# Serqet.net
KiCad netlist of a schematic drawn in EAGLE
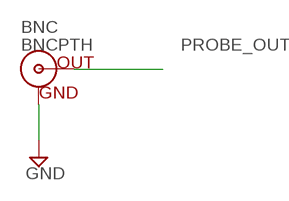
[diagram p0: schematic, sheet 1]
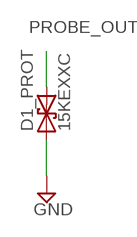
[diagram p1: schematic, sheet 2]
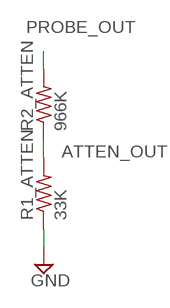
[diagram p2: schematic, sheet 3]
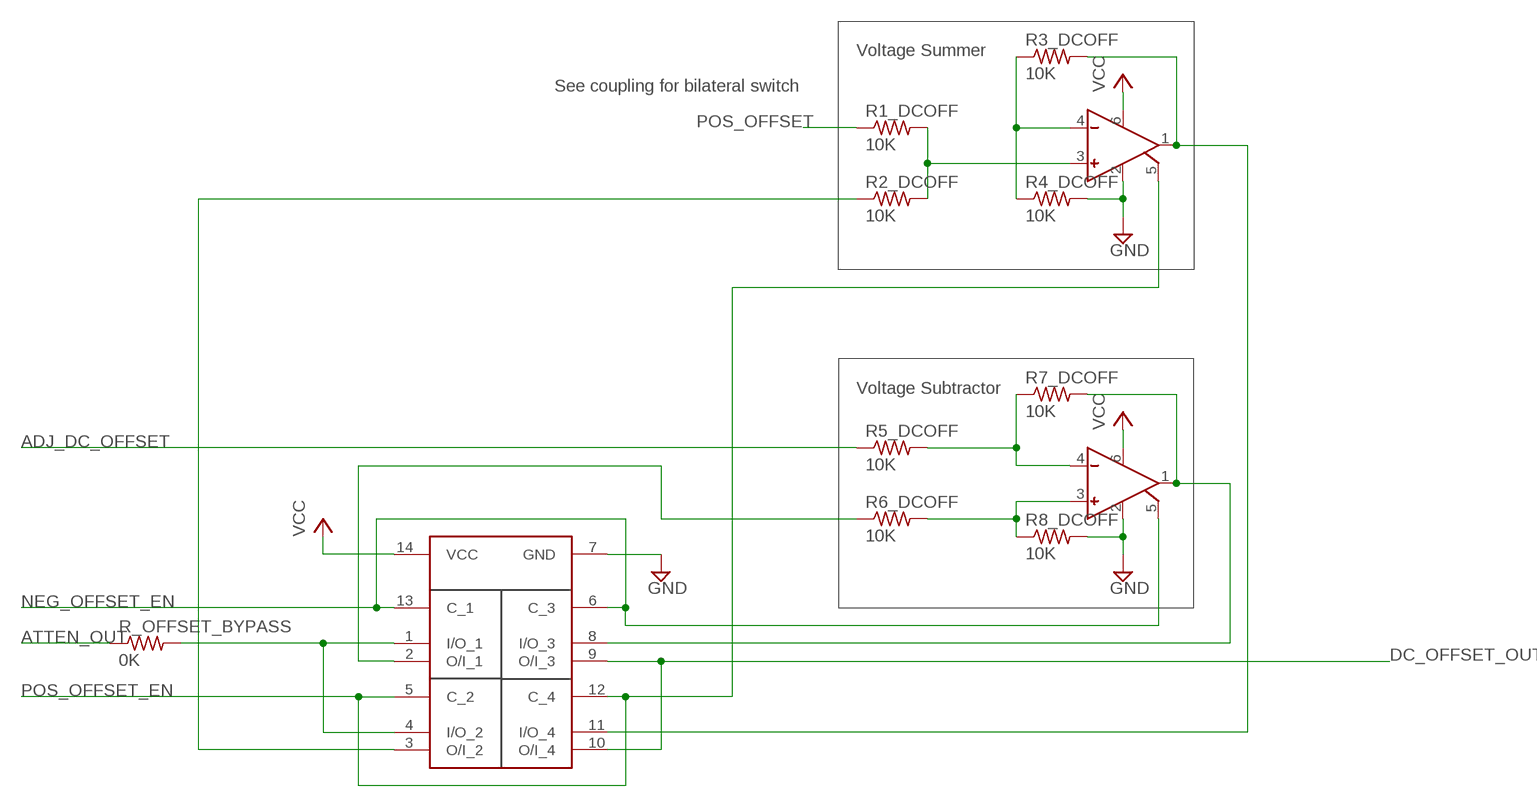
[diagram p3: schematic, sheet 4]
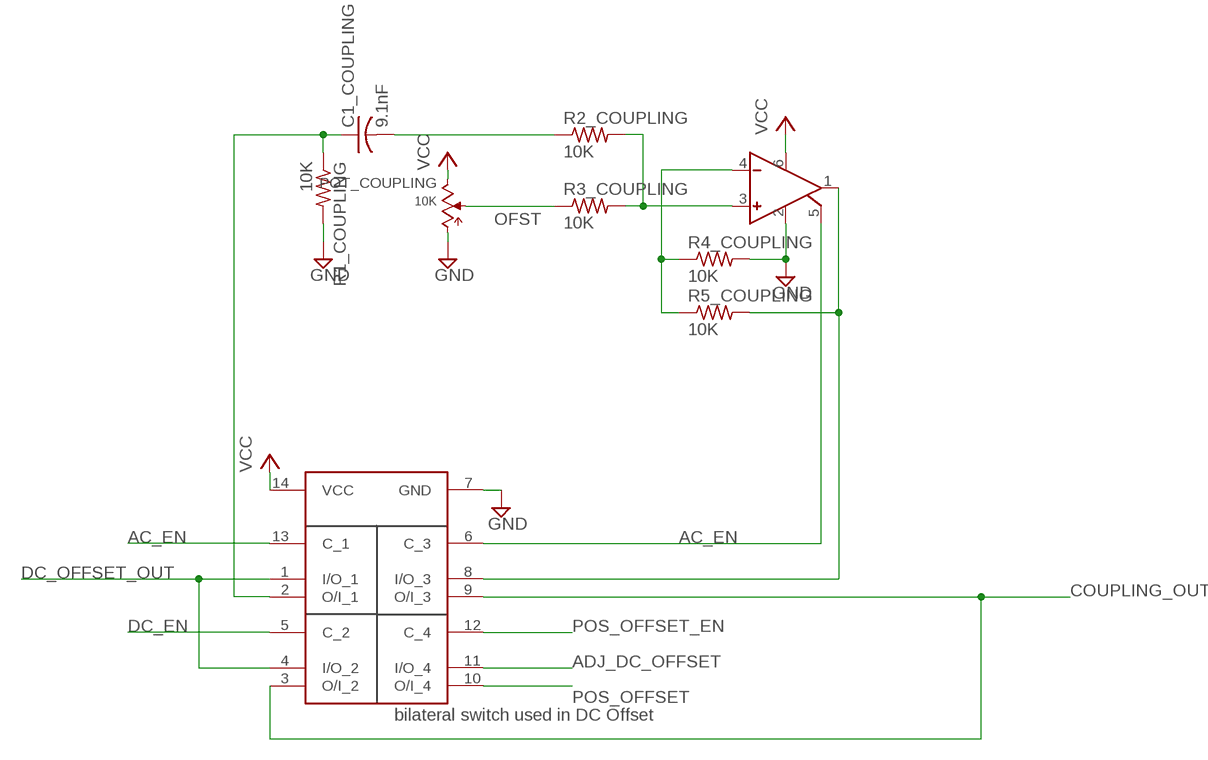
[diagram p4: schematic, sheet 5]
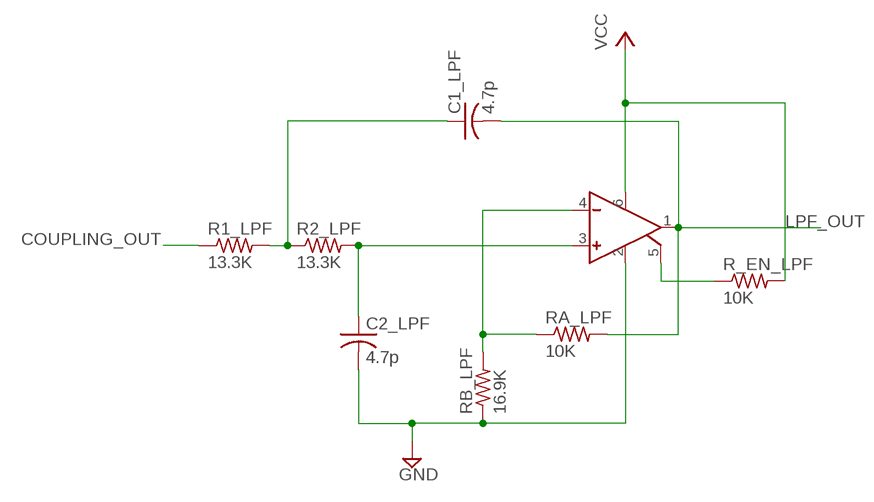
[diagram p5: schematic, sheet 6]
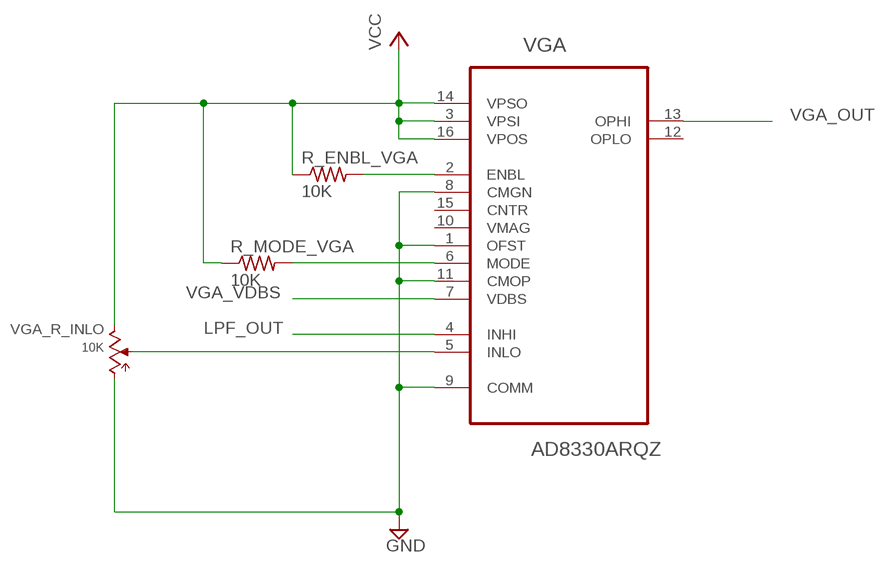
[diagram p6: schematic, sheet 7]
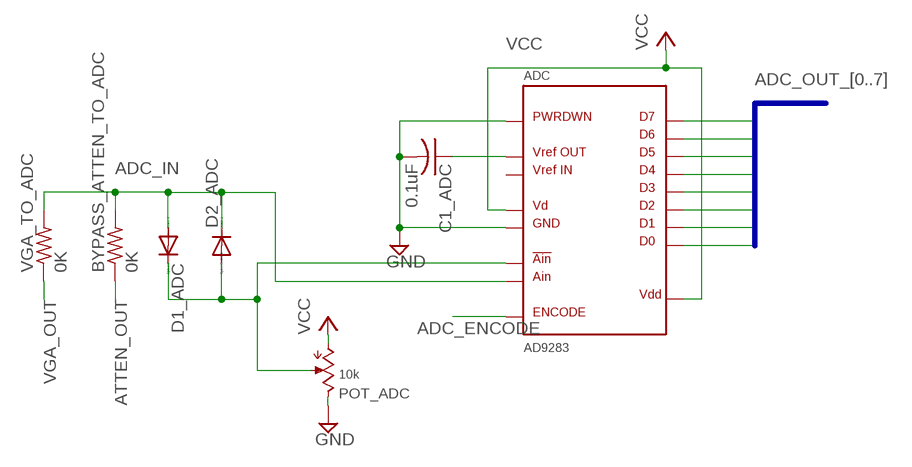
[diagram p7: schematic, sheet 8]
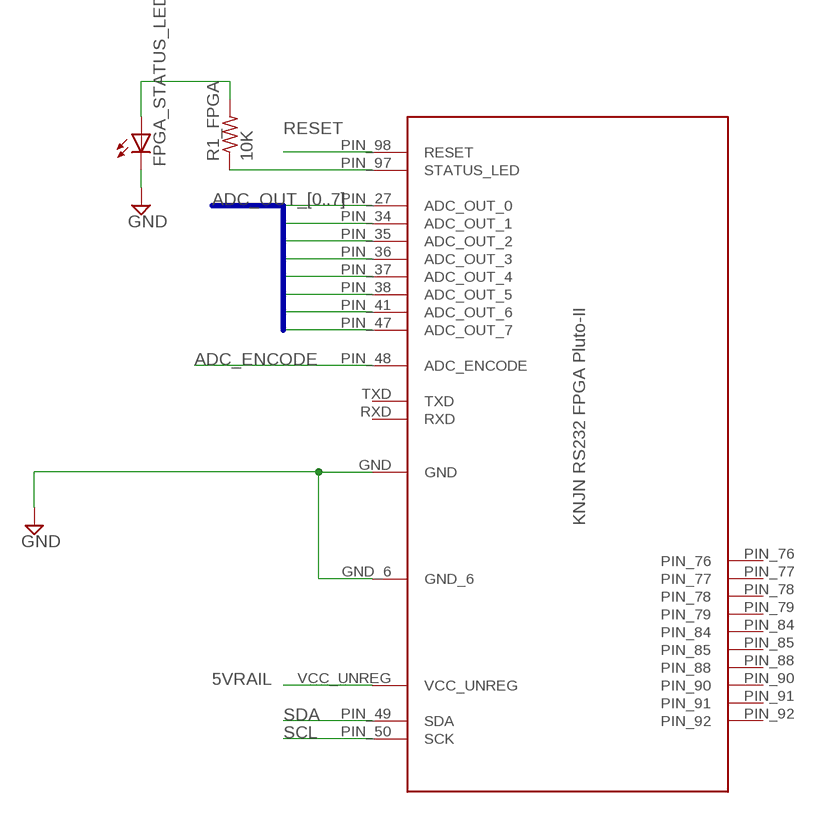
[diagram p8: schematic, sheet 9]
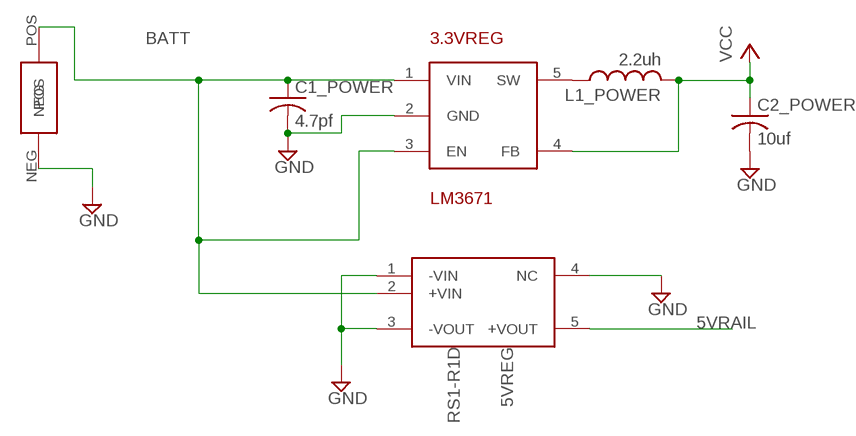
[diagram p9: schematic, sheet 10]
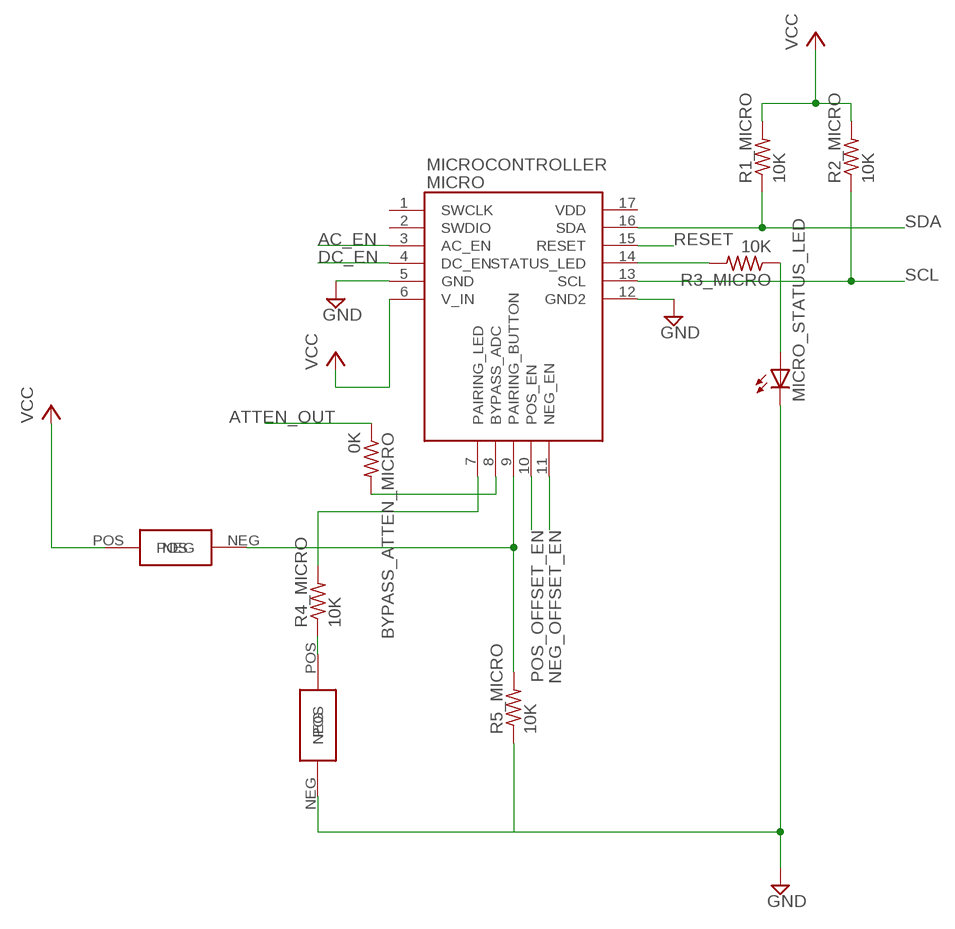
[diagram p10: schematic, sheet 11]
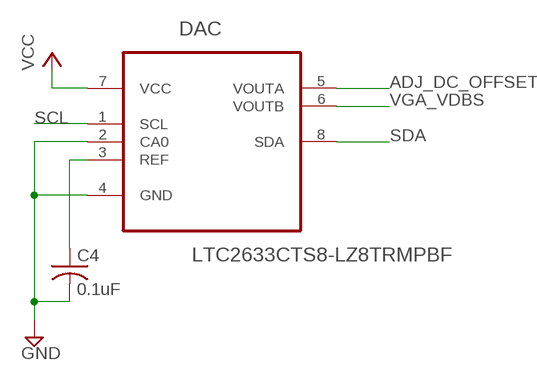
[diagram p11: schematic, sheet 12]

(export (version "E")
  (design (tool "Eeschema 10.0.6"))
  (components
    (comp (ref "BILATERAL_DCOFF")
      (value "TC74HC4066AFT")
      (footprint "eagle-import:TSSOP14")
      (libsource (lib "eagle-import") (part "TC74HC4066AFT"))
    )
    (comp (ref "OP_AMP1_DCOFF")
      (value "OPA355")
      (footprint "eagle-import:SOT23-6")
      (libsource (lib "eagle-import") (part "OPA355"))
    )
    (comp (ref "OP_AMP2_DCOFF")
      (value "OPA355")
      (footprint "eagle-import:SOT23-6")
      (libsource (lib "eagle-import") (part "OPA355"))
    )
    (comp (ref "R1_DCOFF")
      (value "10K")
      (footprint "eagle-import:R0603")
      (libsource (lib "eagle-import") (part "R-US_R0603"))
    )
    (comp (ref "R2_DCOFF")
      (value "10K")
      (footprint "eagle-import:R0603")
      (libsource (lib "eagle-import") (part "R-US_R0603"))
    )
    (comp (ref "R3_DCOFF")
      (value "10K")
      (footprint "eagle-import:R0603")
      (libsource (lib "eagle-import") (part "R-US_R0603"))
    )
    (comp (ref "R4_DCOFF")
      (value "10K")
      (footprint "eagle-import:R0603")
      (libsource (lib "eagle-import") (part "R-US_R0603"))
    )
    (comp (ref "R5_DCOFF")
      (value "10K")
      (footprint "eagle-import:R0603")
      (libsource (lib "eagle-import") (part "R-US_R0603"))
    )
    (comp (ref "R6_DCOFF")
      (value "10K")
      (footprint "eagle-import:R0603")
      (libsource (lib "eagle-import") (part "R-US_R0603"))
    )
    (comp (ref "R7_DCOFF")
      (value "10K")
      (footprint "eagle-import:R0603")
      (libsource (lib "eagle-import") (part "R-US_R0603"))
    )
    (comp (ref "R8_DCOFF")
      (value "10K")
      (footprint "eagle-import:R0603")
      (libsource (lib "eagle-import") (part "R-US_R0603"))
    )
    (comp (ref "R_OFFSET_BYPASS")
      (value "0K")
      (footprint "eagle-import:R0603")
      (libsource (lib "eagle-import") (part "R-US_R0603"))
    )
    (comp (ref "BILATERAL_COUPLING")
      (value "TC74HC4066AFT")
      (footprint "eagle-import:TSSOP14")
      (libsource (lib "eagle-import") (part "TC74HC4066AFT"))
    )
    (comp (ref "C1_COUPLING")
      (value "9.1nF")
      (footprint "eagle-import:C0603")
      (libsource (lib "eagle-import") (part "C-USC0603"))
    )
    (comp (ref "OP_AMP_COUPLING")
      (value "OPA355")
      (footprint "eagle-import:SOT23-6")
      (libsource (lib "eagle-import") (part "OPA355"))
    )
    (comp (ref "POT_COUPLING")
      (value "10K")
      (footprint "eagle-import:TRIMPOT_3HOLE_CHEAP")
      (libsource (lib "eagle-import") (part "POT-CHEAP_3HOLE_TRIM"))
    )
    (comp (ref "R1_COUPLING")
      (value "10K")
      (footprint "eagle-import:R0603")
      (libsource (lib "eagle-import") (part "R-US_R0603"))
    )
    (comp (ref "R2_COUPLING")
      (value "10K")
      (footprint "eagle-import:R0603")
      (libsource (lib "eagle-import") (part "R-US_R0603"))
    )
    (comp (ref "R3_COUPLING")
      (value "10K")
      (footprint "eagle-import:R0603")
      (libsource (lib "eagle-import") (part "R-US_R0603"))
    )
    (comp (ref "R4_COUPLING")
      (value "10K")
      (footprint "eagle-import:R0603")
      (libsource (lib "eagle-import") (part "R-US_R0603"))
    )
    (comp (ref "R5_COUPLING")
      (value "10K")
      (footprint "eagle-import:R0603")
      (libsource (lib "eagle-import") (part "R-US_R0603"))
    )
    (comp (ref "BYPASS_ATTEN_MICRO")
      (value "0K")
      (footprint "eagle-import:R0603")
      (libsource (lib "eagle-import") (part "resistor_R-US_R0603"))
    )
    (comp (ref "LED_THROUGHOLE")
      (value "LED_THROUGHHOLE")
      (footprint "eagle-import:LED_THROUGHHOLE")
      (libsource (lib "eagle-import") (part "LED_THROUGHHOLE"))
    )
    (comp (ref "MICRO")
      (value "MICROCONTROLLER")
      (footprint "eagle-import:MICROPROC")
      (libsource (lib "eagle-import") (part "MICROCONTROLLER"))
    )
    (comp (ref "MICRO_STATUS_LED")
      (value "LEDCHIP-LED0805")
      (footprint "eagle-import:CHIP-LED0805")
      (libsource (lib "eagle-import") (part "LEDCHIP-LED0805"))
    )
    (comp (ref "PAIRING_SWITCH")
      (value "LED_THROUGHHOLE")
      (footprint "eagle-import:LED_THROUGHHOLE")
      (libsource (lib "eagle-import") (part "LED_THROUGHHOLE"))
    )
    (comp (ref "R1_MICRO")
      (value "10K")
      (footprint "eagle-import:R0603")
      (libsource (lib "eagle-import") (part "resistor_R-US_R0603"))
    )
    (comp (ref "R2_MICRO")
      (value "10K")
      (footprint "eagle-import:R0603")
      (libsource (lib "eagle-import") (part "resistor_R-US_R0603"))
    )
    (comp (ref "R3_MICRO")
      (value "10K")
      (footprint "eagle-import:R0603")
      (libsource (lib "eagle-import") (part "resistor_R-US_R0603"))
    )
    (comp (ref "R4_MICRO")
      (value "10K")
      (footprint "eagle-import:R0603")
      (libsource (lib "eagle-import") (part "resistor_R-US_R0603"))
    )
    (comp (ref "R5_MICRO")
      (value "10K")
      (footprint "eagle-import:R0603")
      (libsource (lib "eagle-import") (part "R-US_R0603"))
    )
    (comp (ref "BNC")
      (value "BNCPTH")
      (footprint "eagle-import:BNC")
      (libsource (lib "eagle-import") (part "BNCPTH"))
    )
    (comp (ref "3.3VREG")
      (value "LM3671")
      (footprint "eagle-import:SOT23-5")
      (libsource (lib "eagle-import") (part "LM3671"))
    )
    (comp (ref "5VREG")
      (value "RS1-R1D")
      (footprint "eagle-import:8-SMD")
      (libsource (lib "eagle-import") (part "RS1-R1D"))
    )
    (comp (ref "BATTERY")
      (value "LED_THROUGHHOLE")
      (footprint "eagle-import:LED_THROUGHHOLE")
      (libsource (lib "eagle-import") (part "LED_THROUGHHOLE"))
    )
    (comp (ref "C1_POWER")
      (value "4.7pf")
      (footprint "eagle-import:C0603")
      (libsource (lib "eagle-import") (part "C-USC0603"))
    )
    (comp (ref "C2_POWER")
      (value "10uf")
      (footprint "eagle-import:C0603")
      (libsource (lib "eagle-import") (part "C-USC0603"))
    )
    (comp (ref "L1_POWER")
      (value "2.2uh")
      (footprint "eagle-import:L1812")
      (libsource (lib "eagle-import") (part "L-USL1008"))
    )
    (comp (ref "C1_LPF")
      (value "4.7p")
      (footprint "eagle-import:C0603")
      (libsource (lib "eagle-import") (part "C-USC0603"))
    )
    (comp (ref "C2_LPF")
      (value "4.7p")
      (footprint "eagle-import:C0603")
      (libsource (lib "eagle-import") (part "C-USC0603"))
    )
    (comp (ref "OP_AMP_LPF")
      (value "OPA355")
      (footprint "eagle-import:SOT23-6")
      (libsource (lib "eagle-import") (part "OPA355"))
    )
    (comp (ref "R1_LPF")
      (value "13.3K")
      (footprint "eagle-import:R0603")
      (libsource (lib "eagle-import") (part "R-US_R0603"))
    )
    (comp (ref "R2_LPF")
      (value "13.3K")
      (footprint "eagle-import:R0603")
      (libsource (lib "eagle-import") (part "R-US_R0603"))
    )
    (comp (ref "RA_LPF")
      (value "10K")
      (footprint "eagle-import:R0603")
      (libsource (lib "eagle-import") (part "R-US_R0603"))
    )
    (comp (ref "RB_LPF")
      (value "16.9K")
      (footprint "eagle-import:R0603")
      (libsource (lib "eagle-import") (part "R-US_R0603"))
    )
    (comp (ref "R_EN_LPF")
      (value "10K")
      (footprint "eagle-import:R0603")
      (libsource (lib "eagle-import") (part "R-US_R0603"))
    )
    (comp (ref "FPGA")
      (value "KNJNRS232FPGAPLUTO-IIKNJNRS232FPGAPLUTO-II")
      (footprint "eagle-import:KNJNRS232FPGAPLUTO-II")
      (libsource (lib "eagle-import") (part "KNJNRS232FPGAPLUTO-IIKNJNRS232FPGAPLUTO-II"))
    )
    (comp (ref "FPGA_STATUS_LED")
      (value "LEDCHIP-LED0805")
      (footprint "eagle-import:CHIP-LED0805")
      (libsource (lib "eagle-import") (part "LEDCHIP-LED0805"))
    )
    (comp (ref "R1_FPGA")
      (value "10K")
      (footprint "eagle-import:R0603")
      (libsource (lib "eagle-import") (part "resistor_R-US_R0603"))
    )
    (comp (ref "R_ENBL_VGA")
      (value "10K")
      (footprint "eagle-import:R0603")
      (libsource (lib "eagle-import") (part "R-US_R0603"))
    )
    (comp (ref "R_MODE_VGA")
      (value "10K")
      (footprint "eagle-import:R0603")
      (libsource (lib "eagle-import") (part "R-US_R0603"))
    )
    (comp (ref "VGA")
      (value "AD8330ARQZ")
      (footprint "eagle-import:SOP63P600X175-16N")
      (libsource (lib "eagle-import") (part "AD8330ARQZ"))
    )
    (comp (ref "VGA_R_INLO")
      (value "10K")
      (footprint "eagle-import:TRIMPOT_3HOLE_CHEAP")
      (libsource (lib "eagle-import") (part "POT-CHEAP_3HOLE_TRIM"))
    )
    (comp (ref "ADC")
      (value "AD9283")
      (footprint "eagle-import:SSOP20")
      (libsource (lib "eagle-import") (part "AD9283"))
    )
    (comp (ref "BYPASS_ATTEN_TO_ADC")
      (value "0K")
      (footprint "eagle-import:R0603")
      (libsource (lib "eagle-import") (part "resistor_R-US_R0603"))
    )
    (comp (ref "C1_ADC")
      (value "0.1uF")
      (footprint "eagle-import:C0603")
      (libsource (lib "eagle-import") (part "C-USC0603"))
    )
    (comp (ref "D1_ADC")
      (value "1N4933")
      (footprint "eagle-import:DO41-10")
      (libsource (lib "eagle-import") (part "1N4933"))
    )
    (comp (ref "D2_ADC")
      (value "1N4933")
      (footprint "eagle-import:DO41-10")
      (libsource (lib "eagle-import") (part "1N4933"))
    )
    (comp (ref "POT_ADC")
      (value "10k")
      (footprint "eagle-import:TRIMPOT_3HOLE_CHEAP")
      (libsource (lib "eagle-import") (part "POT-CHEAP_3HOLE_TRIM"))
    )
    (comp (ref "VGA_TO_ADC")
      (value "0K")
      (footprint "eagle-import:R0603")
      (libsource (lib "eagle-import") (part "resistor_R-US_R0603"))
    )
    (comp (ref "C4")
      (value "0.1uF")
      (footprint "eagle-import:C0603")
      (libsource (lib "eagle-import") (part "C-USC0603"))
    )
    (comp (ref "DAC")
      (value "LTC2633CTS8-LZ8TRMPBF")
      (footprint "eagle-import:SOT65P280X100-8N")
      (fields (field (name "MPN") "LTC2633CTS8-LZ8#TRMPBF"))
      (libsource (lib "eagle-import") (part "LTC2633CTS8-LZ8TRMPBF"))
    )
    (comp (ref "D1_PROT")
      (value "15KEXXC")
      (footprint "eagle-import:CB429-17")
      (libsource (lib "eagle-import") (part "15KEXXC"))
    )
    (comp (ref "R1_ATTEN")
      (value "33K")
      (footprint "eagle-import:R0603")
      (libsource (lib "eagle-import") (part "resistor_R-US_R0603"))
    )
    (comp (ref "R2_ATTEN")
      (value "966K")
      (footprint "eagle-import:R0603")
      (libsource (lib "eagle-import") (part "resistor_R-US_R0603"))
    )
  )
  (nets
    (net (code "3") (name "5VRAIL") (class "Default")
      (node (ref "5VREG") (pin "5") (pinfunction "+VOUT_5") (pintype "bidirectional"))
      (node (ref "FPGA") (pin "VCC_UNREG") (pinfunction "VCC_UNREG_VCC_UNREG") (pintype "bidirectional"))
    )
    (net (code "4") (name "AC_EN") (class "Default")
      (node (ref "BILATERAL_COUPLING") (pin "13") (pinfunction "C_1_13") (pintype "bidirectional"))
      (node (ref "BILATERAL_COUPLING") (pin "6") (pinfunction "C_3_6") (pintype "bidirectional"))
      (node (ref "MICRO") (pin "3") (pinfunction "AC_EN_3") (pintype "bidirectional"))
      (node (ref "OP_AMP_COUPLING") (pin "5") (pinfunction "ENABLE_5") (pintype "bidirectional"))
    )
    (net (code "5") (name "ADC_ENCODE") (class "Default")
      (node (ref "ADC") (pin "10") (pinfunction "ENCODE_10") (pintype "input"))
      (node (ref "FPGA") (pin "PIN_48") (pinfunction "ADC_ENCODE_PIN_48") (pintype "bidirectional"))
    )
    (net (code "6") (name "ADC_IN") (class "Default")
      (node (ref "ADC") (pin "7") (pinfunction "AIN_7") (pintype "input"))
      (node (ref "BYPASS_ATTEN_TO_ADC") (pin "2") (pinfunction "2_2") (pintype "passive"))
      (node (ref "D1_ADC") (pin "A") (pinfunction "A_A") (pintype "passive"))
      (node (ref "D2_ADC") (pin "C") (pinfunction "C_C") (pintype "passive"))
      (node (ref "VGA_TO_ADC") (pin "2") (pinfunction "2_2") (pintype "passive"))
    )
    (net (code "7") (name "ADC_OUT_0") (class "Default")
      (node (ref "ADC") (pin "20") (pinfunction "D0_20") (pintype "output"))
      (node (ref "FPGA") (pin "PIN_47") (pinfunction "ADC_OUT_7_PIN_47") (pintype "bidirectional"))
    )
    (net (code "8") (name "ADC_OUT_1") (class "Default")
      (node (ref "ADC") (pin "19") (pinfunction "D1_19") (pintype "output"))
      (node (ref "FPGA") (pin "PIN_41") (pinfunction "ADC_OUT_6_PIN_41") (pintype "bidirectional"))
    )
    (net (code "9") (name "ADC_OUT_2") (class "Default")
      (node (ref "ADC") (pin "18") (pinfunction "D2_18") (pintype "output"))
      (node (ref "FPGA") (pin "PIN_38") (pinfunction "ADC_OUT_5_PIN_38") (pintype "bidirectional"))
    )
    (net (code "10") (name "ADC_OUT_3") (class "Default")
      (node (ref "ADC") (pin "17") (pinfunction "D3_17") (pintype "output"))
      (node (ref "FPGA") (pin "PIN_37") (pinfunction "ADC_OUT_4_PIN_37") (pintype "bidirectional"))
    )
    (net (code "11") (name "ADC_OUT_4") (class "Default")
      (node (ref "ADC") (pin "14") (pinfunction "D4_14") (pintype "output"))
      (node (ref "FPGA") (pin "PIN_36") (pinfunction "ADC_OUT_3_PIN_36") (pintype "bidirectional"))
    )
    (net (code "12") (name "ADC_OUT_5") (class "Default")
      (node (ref "ADC") (pin "13") (pinfunction "D5_13") (pintype "output"))
      (node (ref "FPGA") (pin "PIN_35") (pinfunction "ADC_OUT_2_PIN_35") (pintype "bidirectional"))
    )
    (net (code "13") (name "ADC_OUT_6") (class "Default")
      (node (ref "ADC") (pin "12") (pinfunction "D6_12") (pintype "output"))
      (node (ref "FPGA") (pin "PIN_34") (pinfunction "ADC_OUT_1_PIN_34") (pintype "bidirectional"))
    )
    (net (code "14") (name "ADC_OUT_7") (class "Default")
      (node (ref "ADC") (pin "11") (pinfunction "D7_11") (pintype "output"))
      (node (ref "FPGA") (pin "PIN_27") (pinfunction "ADC_OUT_0_PIN_27") (pintype "bidirectional"))
    )
    (net (code "15") (name "ADJ_DC_OFFSET") (class "Default")
      (node (ref "BILATERAL_COUPLING") (pin "11") (pinfunction "I/O_4_11") (pintype "bidirectional"))
      (node (ref "DAC") (pin "5") (pinfunction "VOUTA_5") (pintype "output"))
      (node (ref "R5_DCOFF") (pin "1") (pinfunction "1_1") (pintype "passive"))
    )
    (net (code "16") (name "ATTEN_OUT") (class "Default")
      (node (ref "BYPASS_ATTEN_MICRO") (pin "1") (pinfunction "1_1") (pintype "passive"))
      (node (ref "BYPASS_ATTEN_TO_ADC") (pin "1") (pinfunction "1_1") (pintype "passive"))
      (node (ref "R1_ATTEN") (pin "2") (pinfunction "2_2") (pintype "passive"))
      (node (ref "R2_ATTEN") (pin "1") (pinfunction "1_1") (pintype "passive"))
      (node (ref "R_OFFSET_BYPASS") (pin "1") (pinfunction "1_1") (pintype "passive"))
    )
    (net (code "17") (name "BATT") (class "Default")
      (node (ref "3.3VREG") (pin "1") (pinfunction "VIN_1") (pintype "bidirectional"))
      (node (ref "3.3VREG") (pin "3") (pinfunction "EN_3") (pintype "bidirectional"))
      (node (ref "5VREG") (pin "2") (pinfunction "+VIN_2") (pintype "bidirectional"))
      (node (ref "BATTERY") (pin "POS") (pinfunction "POS_POS") (pintype "bidirectional"))
      (node (ref "C1_POWER") (pin "1") (pinfunction "1_1") (pintype "passive"))
    )
    (net (code "18") (name "COUPLING_OUT") (class "Default")
      (node (ref "BILATERAL_COUPLING") (pin "3") (pinfunction "O/I_2_3") (pintype "bidirectional"))
      (node (ref "BILATERAL_COUPLING") (pin "9") (pinfunction "O/I_3_9") (pintype "bidirectional"))
      (node (ref "R1_LPF") (pin "1") (pinfunction "1_1") (pintype "passive"))
    )
    (net (code "19") (name "DC_EN") (class "Default")
      (node (ref "BILATERAL_COUPLING") (pin "5") (pinfunction "C_2_5") (pintype "bidirectional"))
      (node (ref "MICRO") (pin "4") (pinfunction "DC_EN_4") (pintype "bidirectional"))
    )
    (net (code "20") (name "DC_OFFSET_OUT") (class "Default")
      (node (ref "BILATERAL_COUPLING") (pin "1") (pinfunction "I/O_1_1") (pintype "bidirectional"))
      (node (ref "BILATERAL_COUPLING") (pin "4") (pinfunction "I/O_2_4") (pintype "bidirectional"))
      (node (ref "BILATERAL_DCOFF") (pin "10") (pinfunction "O/I_4_10") (pintype "bidirectional"))
      (node (ref "BILATERAL_DCOFF") (pin "9") (pinfunction "O/I_3_9") (pintype "bidirectional"))
    )
    (net (code "21") (name "GND") (class "Default")
      (node (ref "3.3VREG") (pin "2") (pinfunction "GND_2") (pintype "bidirectional"))
      (node (ref "5VREG") (pin "1") (pinfunction "-VIN_1") (pintype "bidirectional"))
      (node (ref "5VREG") (pin "3") (pinfunction "-VOUT_3") (pintype "bidirectional"))
      (node (ref "5VREG") (pin "4") (pinfunction "NC_4") (pintype "bidirectional"))
      (node (ref "ADC") (pin "1") (pinfunction "PWRDWN_1") (pintype "input"))
      (node (ref "ADC") (pin "16") (pinfunction "GND_16") (pintype "power_in"))
      (node (ref "ADC") (pin "4") (pinfunction "GND_4") (pintype "power_in"))
      (node (ref "ADC") (pin "9") (pinfunction "GND_9") (pintype "power_in"))
      (node (ref "BATTERY") (pin "NEG") (pinfunction "NEG_NEG") (pintype "bidirectional"))
      (node (ref "BILATERAL_COUPLING") (pin "7") (pinfunction "GND_7") (pintype "bidirectional"))
      (node (ref "BILATERAL_DCOFF") (pin "7") (pinfunction "GND_7") (pintype "bidirectional"))
      (node (ref "BNC") (pin "GND") (pinfunction "GND_GND") (pintype "bidirectional"))
      (node (ref "C1_ADC") (pin "2") (pinfunction "2_2") (pintype "passive"))
      (node (ref "C1_POWER") (pin "2") (pinfunction "2_2") (pintype "passive"))
      (node (ref "C2_LPF") (pin "2") (pinfunction "2_2") (pintype "passive"))
      (node (ref "C2_POWER") (pin "2") (pinfunction "2_2") (pintype "passive"))
      (node (ref "C4") (pin "2") (pinfunction "2_2") (pintype "passive"))
      (node (ref "D1_PROT") (pin "A") (pinfunction "1_A") (pintype "passive"))
      (node (ref "DAC") (pin "2") (pinfunction "CA0_2") (pintype "input"))
      (node (ref "DAC") (pin "4") (pinfunction "GND_4") (pintype "passive"))
      (node (ref "FPGA") (pin "GND") (pinfunction "GND_GND") (pintype "bidirectional"))
      (node (ref "FPGA") (pin "GND_6") (pinfunction "GND_6_GND_6") (pintype "bidirectional"))
      (node (ref "FPGA_STATUS_LED") (pin "C") (pinfunction "C_C") (pintype "passive"))
      (node (ref "LED_THROUGHOLE") (pin "NEG") (pinfunction "NEG_NEG") (pintype "bidirectional"))
      (node (ref "MICRO") (pin "12") (pinfunction "GND2_12") (pintype "bidirectional"))
      (node (ref "MICRO") (pin "5") (pinfunction "GND_5") (pintype "bidirectional"))
      (node (ref "MICRO_STATUS_LED") (pin "C") (pinfunction "C_C") (pintype "passive"))
      (node (ref "OP_AMP1_DCOFF") (pin "2") (pinfunction "GND_2") (pintype "bidirectional"))
      (node (ref "OP_AMP2_DCOFF") (pin "2") (pinfunction "GND_2") (pintype "bidirectional"))
      (node (ref "OP_AMP_COUPLING") (pin "2") (pinfunction "GND_2") (pintype "bidirectional"))
      (node (ref "OP_AMP_LPF") (pin "2") (pinfunction "GND_2") (pintype "bidirectional"))
      (node (ref "POT_ADC") (pin "CW") (pinfunction "CW_CW") (pintype "bidirectional"))
      (node (ref "POT_COUPLING") (pin "CCW") (pinfunction "CCW_CCW") (pintype "bidirectional"))
      (node (ref "R1_ATTEN") (pin "1") (pinfunction "1_1") (pintype "passive"))
      (node (ref "R1_COUPLING") (pin "2") (pinfunction "2_2") (pintype "passive"))
      (node (ref "R4_COUPLING") (pin "2") (pinfunction "2_2") (pintype "passive"))
      (node (ref "R4_DCOFF") (pin "2") (pinfunction "2_2") (pintype "passive"))
      (node (ref "R5_MICRO") (pin "1") (pinfunction "1_1") (pintype "passive"))
      (node (ref "R8_DCOFF") (pin "2") (pinfunction "2_2") (pintype "passive"))
      (node (ref "RB_LPF") (pin "1") (pinfunction "1_1") (pintype "passive"))
      (node (ref "VGA") (pin "1") (pinfunction "OFST_1") (pintype "passive"))
      (node (ref "VGA") (pin "11") (pinfunction "CMOP_11") (pintype "passive"))
      (node (ref "VGA") (pin "8") (pinfunction "CMGN_8") (pintype "passive"))
      (node (ref "VGA") (pin "9") (pinfunction "COMM_9") (pintype "input"))
      (node (ref "VGA_R_INLO") (pin "CCW") (pinfunction "CCW_CCW") (pintype "bidirectional"))
    )
    (net (code "22") (name "LPF_OUT") (class "Default")
      (node (ref "C1_LPF") (pin "2") (pinfunction "2_2") (pintype "passive"))
      (node (ref "OP_AMP_LPF") (pin "1") (pinfunction "OUT_1") (pintype "bidirectional"))
      (node (ref "RA_LPF") (pin "2") (pinfunction "2_2") (pintype "passive"))
      (node (ref "VGA") (pin "4") (pinfunction "INHI_4") (pintype "input"))
    )
    (net (code "23") (name "N$22") (class "Default")
      (node (ref "BILATERAL_DCOFF") (pin "3") (pinfunction "O/I_2_3") (pintype "bidirectional"))
      (node (ref "MICRO") (pin "9") (pinfunction "PAIRING_BUTTON_9") (pintype "bidirectional"))
      (node (ref "PAIRING_SWITCH") (pin "NEG") (pinfunction "NEG_NEG") (pintype "bidirectional"))
      (node (ref "R2_DCOFF") (pin "1") (pinfunction "1_1") (pintype "passive"))
      (node (ref "R5_MICRO") (pin "2") (pinfunction "2_2") (pintype "passive"))
    )
    (net (code "24") (name "NEG_OFFSET_EN") (class "Default")
      (node (ref "BILATERAL_DCOFF") (pin "13") (pinfunction "C_1_13") (pintype "bidirectional"))
      (node (ref "BILATERAL_DCOFF") (pin "6") (pinfunction "C_3_6") (pintype "bidirectional"))
      (node (ref "MICRO") (pin "11") (pinfunction "NEG_EN_11") (pintype "bidirectional"))
      (node (ref "OP_AMP2_DCOFF") (pin "5") (pinfunction "ENABLE_5") (pintype "bidirectional"))
    )
    (net (code "25") (name "Net-(3.3VREG-SW)") (class "Default")
      (node (ref "3.3VREG") (pin "5") (pinfunction "SW_5") (pintype "bidirectional"))
      (node (ref "L1_POWER") (pin "1") (pinfunction "1_1") (pintype "passive"))
    )
    (net (code "26") (name "Net-(ADC-VREFOUT)") (class "Default")
      (node (ref "ADC") (pin "2") (pinfunction "VREFOUT_2") (pintype "power_in"))
      (node (ref "C1_ADC") (pin "1") (pinfunction "1_1") (pintype "passive"))
    )
    (net (code "27") (name "Net-(ADC-~{AIN})") (class "Default")
      (node (ref "ADC") (pin "6") (pinfunction "~{AIN}_6") (pintype "input"))
      (node (ref "D1_ADC") (pin "C") (pinfunction "C_C") (pintype "passive"))
      (node (ref "D2_ADC") (pin "A") (pinfunction "A_A") (pintype "passive"))
      (node (ref "POT_ADC") (pin "W") (pinfunction "W_W") (pintype "bidirectional"))
    )
    (net (code "28") (name "Net-(BILATERAL_COUPLING-I{slash}O_3)") (class "Default")
      (node (ref "BILATERAL_COUPLING") (pin "8") (pinfunction "I/O_3_8") (pintype "bidirectional"))
      (node (ref "OP_AMP_COUPLING") (pin "1") (pinfunction "OUT_1") (pintype "bidirectional"))
      (node (ref "R5_COUPLING") (pin "2") (pinfunction "2_2") (pintype "passive"))
    )
    (net (code "29") (name "Net-(BILATERAL_COUPLING-O{slash}I_1)") (class "Default")
      (node (ref "BILATERAL_COUPLING") (pin "2") (pinfunction "O/I_1_2") (pintype "bidirectional"))
      (node (ref "C1_COUPLING") (pin "1") (pinfunction "1_1") (pintype "passive"))
      (node (ref "R1_COUPLING") (pin "1") (pinfunction "1_1") (pintype "passive"))
    )
    (net (code "30") (name "Net-(BILATERAL_DCOFF-I{slash}O_1)") (class "Default")
      (node (ref "BILATERAL_DCOFF") (pin "1") (pinfunction "I/O_1_1") (pintype "bidirectional"))
      (node (ref "BILATERAL_DCOFF") (pin "4") (pinfunction "I/O_2_4") (pintype "bidirectional"))
      (node (ref "R_OFFSET_BYPASS") (pin "2") (pinfunction "2_2") (pintype "passive"))
    )
    (net (code "31") (name "Net-(BILATERAL_DCOFF-I{slash}O_3)") (class "Default")
      (node (ref "BILATERAL_DCOFF") (pin "8") (pinfunction "I/O_3_8") (pintype "bidirectional"))
      (node (ref "OP_AMP2_DCOFF") (pin "1") (pinfunction "OUT_1") (pintype "bidirectional"))
      (node (ref "R7_DCOFF") (pin "2") (pinfunction "2_2") (pintype "passive"))
    )
    (net (code "32") (name "Net-(BILATERAL_DCOFF-I{slash}O_4)") (class "Default")
      (node (ref "BILATERAL_DCOFF") (pin "11") (pinfunction "I/O_4_11") (pintype "bidirectional"))
      (node (ref "OP_AMP1_DCOFF") (pin "1") (pinfunction "OUT_1") (pintype "bidirectional"))
      (node (ref "R3_DCOFF") (pin "2") (pinfunction "2_2") (pintype "passive"))
    )
    (net (code "33") (name "Net-(BILATERAL_DCOFF-O{slash}I_1)") (class "Default")
      (node (ref "BILATERAL_DCOFF") (pin "2") (pinfunction "O/I_1_2") (pintype "bidirectional"))
      (node (ref "R6_DCOFF") (pin "1") (pinfunction "1_1") (pintype "passive"))
    )
    (net (code "34") (name "Net-(C1_COUPLING-Pad2)") (class "Default")
      (node (ref "C1_COUPLING") (pin "2") (pinfunction "2_2") (pintype "passive"))
      (node (ref "R2_COUPLING") (pin "1") (pinfunction "1_1") (pintype "passive"))
    )
    (net (code "35") (name "Net-(C1_LPF-Pad1)") (class "Default")
      (node (ref "C1_LPF") (pin "1") (pinfunction "1_1") (pintype "passive"))
      (node (ref "R1_LPF") (pin "2") (pinfunction "2_2") (pintype "passive"))
      (node (ref "R2_LPF") (pin "1") (pinfunction "1_1") (pintype "passive"))
    )
    (net (code "36") (name "Net-(DAC-REF)") (class "Default")
      (node (ref "C4") (pin "1") (pinfunction "1_1") (pintype "passive"))
      (node (ref "DAC") (pin "3") (pinfunction "REF_3") (pintype "input"))
    )
    (net (code "37") (name "Net-(FPGA-STATUS_LED)") (class "Default")
      (node (ref "FPGA") (pin "PIN_97") (pinfunction "STATUS_LED_PIN_97") (pintype "bidirectional"))
      (node (ref "R1_FPGA") (pin "1") (pinfunction "1_1") (pintype "passive"))
    )
    (net (code "38") (name "Net-(FPGA_STATUS_LED-PadA)") (class "Default")
      (node (ref "FPGA_STATUS_LED") (pin "A") (pinfunction "A_A") (pintype "passive"))
      (node (ref "R1_FPGA") (pin "2") (pinfunction "2_2") (pintype "passive"))
    )
    (net (code "39") (name "Net-(LED_THROUGHOLE-PadPOS)") (class "Default")
      (node (ref "LED_THROUGHOLE") (pin "POS") (pinfunction "POS_POS") (pintype "bidirectional"))
      (node (ref "R4_MICRO") (pin "1") (pinfunction "1_1") (pintype "passive"))
    )
    (net (code "40") (name "Net-(MICRO-BYPASS_ADC)") (class "Default")
      (node (ref "BYPASS_ATTEN_MICRO") (pin "2") (pinfunction "2_2") (pintype "passive"))
      (node (ref "MICRO") (pin "8") (pinfunction "BYPASS_ADC_8") (pintype "bidirectional"))
    )
    (net (code "41") (name "Net-(MICRO-PAIRING_LED)") (class "Default")
      (node (ref "MICRO") (pin "7") (pinfunction "PAIRING_LED_7") (pintype "bidirectional"))
      (node (ref "R4_MICRO") (pin "2") (pinfunction "2_2") (pintype "passive"))
    )
    (net (code "42") (name "Net-(MICRO-STATUS_LED)") (class "Default")
      (node (ref "MICRO") (pin "14") (pinfunction "STATUS_LED_14") (pintype "bidirectional"))
      (node (ref "R3_MICRO") (pin "2") (pinfunction "2_2") (pintype "passive"))
    )
    (net (code "43") (name "Net-(MICRO_STATUS_LED-PadA)") (class "Default")
      (node (ref "MICRO_STATUS_LED") (pin "A") (pinfunction "A_A") (pintype "passive"))
      (node (ref "R3_MICRO") (pin "1") (pinfunction "1_1") (pintype "passive"))
    )
    (net (code "44") (name "Net-(OP_AMP1_DCOFF-V+)") (class "Default")
      (node (ref "OP_AMP1_DCOFF") (pin "3") (pinfunction "V+_3") (pintype "bidirectional"))
      (node (ref "R1_DCOFF") (pin "2") (pinfunction "2_2") (pintype "passive"))
      (node (ref "R2_DCOFF") (pin "2") (pinfunction "2_2") (pintype "passive"))
    )
    (net (code "45") (name "Net-(OP_AMP1_DCOFF-V-)") (class "Default")
      (node (ref "OP_AMP1_DCOFF") (pin "4") (pinfunction "V-_4") (pintype "bidirectional"))
      (node (ref "R3_DCOFF") (pin "1") (pinfunction "1_1") (pintype "passive"))
      (node (ref "R4_DCOFF") (pin "1") (pinfunction "1_1") (pintype "passive"))
    )
    (net (code "46") (name "Net-(OP_AMP2_DCOFF-V+)") (class "Default")
      (node (ref "OP_AMP2_DCOFF") (pin "3") (pinfunction "V+_3") (pintype "bidirectional"))
      (node (ref "R6_DCOFF") (pin "2") (pinfunction "2_2") (pintype "passive"))
      (node (ref "R8_DCOFF") (pin "1") (pinfunction "1_1") (pintype "passive"))
    )
    (net (code "47") (name "Net-(OP_AMP2_DCOFF-V-)") (class "Default")
      (node (ref "OP_AMP2_DCOFF") (pin "4") (pinfunction "V-_4") (pintype "bidirectional"))
      (node (ref "R5_DCOFF") (pin "2") (pinfunction "2_2") (pintype "passive"))
      (node (ref "R7_DCOFF") (pin "1") (pinfunction "1_1") (pintype "passive"))
    )
    (net (code "48") (name "Net-(OP_AMP_COUPLING-V+)") (class "Default")
      (node (ref "OP_AMP_COUPLING") (pin "3") (pinfunction "V+_3") (pintype "bidirectional"))
      (node (ref "R2_COUPLING") (pin "2") (pinfunction "2_2") (pintype "passive"))
      (node (ref "R3_COUPLING") (pin "2") (pinfunction "2_2") (pintype "passive"))
    )
    (net (code "49") (name "Net-(OP_AMP_COUPLING-V-)") (class "Default")
      (node (ref "OP_AMP_COUPLING") (pin "4") (pinfunction "V-_4") (pintype "bidirectional"))
      (node (ref "R4_COUPLING") (pin "1") (pinfunction "1_1") (pintype "passive"))
      (node (ref "R5_COUPLING") (pin "1") (pinfunction "1_1") (pintype "passive"))
    )
    (net (code "50") (name "Net-(OP_AMP_LPF-ENABLE)") (class "Default")
      (node (ref "OP_AMP_LPF") (pin "5") (pinfunction "ENABLE_5") (pintype "bidirectional"))
      (node (ref "R_EN_LPF") (pin "1") (pinfunction "1_1") (pintype "passive"))
    )
    (net (code "51") (name "Net-(OP_AMP_LPF-V+)") (class "Default")
      (node (ref "C2_LPF") (pin "1") (pinfunction "1_1") (pintype "passive"))
      (node (ref "OP_AMP_LPF") (pin "3") (pinfunction "V+_3") (pintype "bidirectional"))
      (node (ref "R2_LPF") (pin "2") (pinfunction "2_2") (pintype "passive"))
    )
    (net (code "52") (name "Net-(OP_AMP_LPF-V-)") (class "Default")
      (node (ref "OP_AMP_LPF") (pin "4") (pinfunction "V-_4") (pintype "bidirectional"))
      (node (ref "RA_LPF") (pin "1") (pinfunction "1_1") (pintype "passive"))
      (node (ref "RB_LPF") (pin "2") (pinfunction "2_2") (pintype "passive"))
    )
    (net (code "53") (name "Net-(VGA-ENBL)") (class "Default")
      (node (ref "R_ENBL_VGA") (pin "2") (pinfunction "2_2") (pintype "passive"))
      (node (ref "VGA") (pin "2") (pinfunction "ENBL_2") (pintype "input"))
    )
    (net (code "54") (name "Net-(VGA-INLO)") (class "Default")
      (node (ref "VGA") (pin "5") (pinfunction "INLO_5") (pintype "input"))
      (node (ref "VGA_R_INLO") (pin "W") (pinfunction "W_W") (pintype "bidirectional"))
    )
    (net (code "55") (name "Net-(VGA-MODE)") (class "Default")
      (node (ref "R_MODE_VGA") (pin "2") (pinfunction "2_2") (pintype "passive"))
      (node (ref "VGA") (pin "6") (pinfunction "MODE_6") (pintype "input"))
    )
    (net (code "56") (name "OFST") (class "Default")
      (node (ref "POT_COUPLING") (pin "W") (pinfunction "W_W") (pintype "bidirectional"))
      (node (ref "R3_COUPLING") (pin "1") (pinfunction "1_1") (pintype "passive"))
    )
    (net (code "57") (name "POS_OFFSET") (class "Default")
      (node (ref "BILATERAL_COUPLING") (pin "10") (pinfunction "O/I_4_10") (pintype "bidirectional"))
      (node (ref "R1_DCOFF") (pin "1") (pinfunction "1_1") (pintype "passive"))
    )
    (net (code "58") (name "POS_OFFSET_EN") (class "Default")
      (node (ref "BILATERAL_COUPLING") (pin "12") (pinfunction "C_4_12") (pintype "bidirectional"))
      (node (ref "BILATERAL_DCOFF") (pin "12") (pinfunction "C_4_12") (pintype "bidirectional"))
      (node (ref "BILATERAL_DCOFF") (pin "5") (pinfunction "C_2_5") (pintype "bidirectional"))
      (node (ref "MICRO") (pin "10") (pinfunction "POS_EN_10") (pintype "bidirectional"))
      (node (ref "OP_AMP1_DCOFF") (pin "5") (pinfunction "ENABLE_5") (pintype "bidirectional"))
    )
    (net (code "59") (name "PROBE_OUT") (class "Default")
      (node (ref "BNC") (pin "S") (pinfunction "OUT_S") (pintype "bidirectional"))
      (node (ref "D1_PROT") (pin "C") (pinfunction "2_C") (pintype "passive"))
      (node (ref "R2_ATTEN") (pin "2") (pinfunction "2_2") (pintype "passive"))
    )
    (net (code "60") (name "RESET") (class "Default")
      (node (ref "FPGA") (pin "PIN_98") (pinfunction "RESET_PIN_98") (pintype "bidirectional"))
      (node (ref "MICRO") (pin "15") (pinfunction "RESET_15") (pintype "bidirectional"))
    )
    (net (code "61") (name "SCL") (class "Default")
      (node (ref "DAC") (pin "1") (pinfunction "SCL_1") (pintype "input"))
      (node (ref "FPGA") (pin "PIN_50") (pinfunction "SCK_PIN_50") (pintype "bidirectional"))
      (node (ref "MICRO") (pin "13") (pinfunction "SCL_13") (pintype "bidirectional"))
      (node (ref "R2_MICRO") (pin "1") (pinfunction "1_1") (pintype "passive"))
    )
    (net (code "62") (name "SDA") (class "Default")
      (node (ref "DAC") (pin "8") (pinfunction "SDA_8") (pintype "bidirectional"))
      (node (ref "FPGA") (pin "PIN_49") (pinfunction "SDA_PIN_49") (pintype "bidirectional"))
      (node (ref "MICRO") (pin "16") (pinfunction "SDA_16") (pintype "bidirectional"))
      (node (ref "R1_MICRO") (pin "1") (pinfunction "1_1") (pintype "passive"))
    )
    (net (code "63") (name "VCC") (class "Default")
      (node (ref "3.3VREG") (pin "4") (pinfunction "FB_4") (pintype "bidirectional"))
      (node (ref "ADC") (pin "15") (pinfunction "VDD_15") (pintype "power_in"))
      (node (ref "ADC") (pin "5") (pinfunction "VD_5") (pintype "power_in"))
      (node (ref "ADC") (pin "8") (pinfunction "VD_8") (pintype "power_in"))
      (node (ref "BILATERAL_COUPLING") (pin "14") (pinfunction "VCC_14") (pintype "bidirectional"))
      (node (ref "BILATERAL_DCOFF") (pin "14") (pinfunction "VCC_14") (pintype "bidirectional"))
      (node (ref "C2_POWER") (pin "1") (pinfunction "1_1") (pintype "passive"))
      (node (ref "DAC") (pin "7") (pinfunction "VCC_7") (pintype "power_in"))
      (node (ref "L1_POWER") (pin "2") (pinfunction "2_2") (pintype "passive"))
      (node (ref "MICRO") (pin "6") (pinfunction "V_IN_6") (pintype "bidirectional"))
      (node (ref "OP_AMP1_DCOFF") (pin "6") (pinfunction "VCC_6") (pintype "bidirectional"))
      (node (ref "OP_AMP2_DCOFF") (pin "6") (pinfunction "VCC_6") (pintype "bidirectional"))
      (node (ref "OP_AMP_COUPLING") (pin "6") (pinfunction "VCC_6") (pintype "bidirectional"))
      (node (ref "OP_AMP_LPF") (pin "6") (pinfunction "VCC_6") (pintype "bidirectional"))
      (node (ref "PAIRING_SWITCH") (pin "POS") (pinfunction "POS_POS") (pintype "bidirectional"))
      (node (ref "POT_ADC") (pin "CCW") (pinfunction "CCW_CCW") (pintype "bidirectional"))
      (node (ref "POT_COUPLING") (pin "CW") (pinfunction "CW_CW") (pintype "bidirectional"))
      (node (ref "R1_MICRO") (pin "2") (pinfunction "2_2") (pintype "passive"))
      (node (ref "R2_MICRO") (pin "2") (pinfunction "2_2") (pintype "passive"))
      (node (ref "R_ENBL_VGA") (pin "1") (pinfunction "1_1") (pintype "passive"))
      (node (ref "R_EN_LPF") (pin "2") (pinfunction "2_2") (pintype "passive"))
      (node (ref "R_MODE_VGA") (pin "1") (pinfunction "1_1") (pintype "passive"))
      (node (ref "VGA") (pin "14") (pinfunction "VPSO_14") (pintype "power_in"))
      (node (ref "VGA") (pin "16") (pinfunction "VPOS_16") (pintype "power_in"))
      (node (ref "VGA") (pin "3") (pinfunction "VPSI_3") (pintype "power_in"))
      (node (ref "VGA_R_INLO") (pin "CW") (pinfunction "CW_CW") (pintype "bidirectional"))
    )
    (net (code "64") (name "VGA_OUT") (class "Default")
      (node (ref "VGA") (pin "13") (pinfunction "OPHI_13") (pintype "output"))
      (node (ref "VGA_TO_ADC") (pin "1") (pinfunction "1_1") (pintype "passive"))
    )
    (net (code "65") (name "VGA_VDBS") (class "Default")
      (node (ref "DAC") (pin "6") (pinfunction "VOUTB_6") (pintype "output"))
      (node (ref "VGA") (pin "7") (pinfunction "VDBS_7") (pintype "input"))
    )
    (net (code "66") (name "VREFIN") (class "Default")
      (node (ref "ADC") (pin "3") (pinfunction "VREFIN_3") (pintype "power_in"))
    )
    (net (code "67") (name "unconnected-(FPGA-PadPIN_76)") (class "Default")
      (node (ref "FPGA") (pin "PIN_76") (pinfunction "PIN_76_PIN_76") (pintype "bidirectional"))
    )
    (net (code "68") (name "unconnected-(FPGA-PadPIN_77)") (class "Default")
      (node (ref "FPGA") (pin "PIN_77") (pinfunction "PIN_77_PIN_77") (pintype "bidirectional"))
    )
    (net (code "69") (name "unconnected-(FPGA-PadPIN_78)") (class "Default")
      (node (ref "FPGA") (pin "PIN_78") (pinfunction "PIN_78_PIN_78") (pintype "bidirectional"))
    )
    (net (code "70") (name "unconnected-(FPGA-PadPIN_79)") (class "Default")
      (node (ref "FPGA") (pin "PIN_79") (pinfunction "PIN_79_PIN_79") (pintype "bidirectional"))
    )
    (net (code "71") (name "unconnected-(FPGA-PadPIN_84)") (class "Default")
      (node (ref "FPGA") (pin "PIN_84") (pinfunction "PIN_84_PIN_84") (pintype "bidirectional"))
    )
    (net (code "72") (name "unconnected-(FPGA-PadPIN_85)") (class "Default")
      (node (ref "FPGA") (pin "PIN_85") (pinfunction "PIN_85_PIN_85") (pintype "bidirectional"))
    )
    (net (code "73") (name "unconnected-(FPGA-PadPIN_88)") (class "Default")
      (node (ref "FPGA") (pin "PIN_88") (pinfunction "PIN_88_PIN_88") (pintype "bidirectional"))
    )
    (net (code "74") (name "unconnected-(FPGA-PadPIN_90)") (class "Default")
      (node (ref "FPGA") (pin "PIN_90") (pinfunction "PIN_90_PIN_90") (pintype "bidirectional"))
    )
    (net (code "75") (name "unconnected-(FPGA-PadPIN_91)") (class "Default")
      (node (ref "FPGA") (pin "PIN_91") (pinfunction "PIN_91_PIN_91") (pintype "bidirectional"))
    )
    (net (code "76") (name "unconnected-(FPGA-PadPIN_92)") (class "Default")
      (node (ref "FPGA") (pin "PIN_92") (pinfunction "PIN_92_PIN_92") (pintype "bidirectional"))
    )
    (net (code "77") (name "unconnected-(FPGA-PadRXD)") (class "Default")
      (node (ref "FPGA") (pin "RXD") (pinfunction "RXD_RXD") (pintype "bidirectional"))
    )
    (net (code "78") (name "unconnected-(FPGA-PadTXD)") (class "Default")
      (node (ref "FPGA") (pin "TXD") (pinfunction "TXD_TXD") (pintype "bidirectional"))
    )
    (net (code "79") (name "unconnected-(MICRO-SWCLK-Pad1)") (class "Default")
      (node (ref "MICRO") (pin "1") (pinfunction "SWCLK_1") (pintype "bidirectional"))
    )
    (net (code "80") (name "unconnected-(MICRO-SWDIO-Pad2)") (class "Default")
      (node (ref "MICRO") (pin "2") (pinfunction "SWDIO_2") (pintype "bidirectional"))
    )
    (net (code "81") (name "unconnected-(MICRO-VDD-Pad17)") (class "Default")
      (node (ref "MICRO") (pin "17") (pinfunction "VDD_17") (pintype "bidirectional"))
    )
    (net (code "82") (name "unconnected-(VGA-CNTR-Pad15)") (class "Default")
      (node (ref "VGA") (pin "15") (pinfunction "CNTR_15") (pintype "input"))
    )
    (net (code "83") (name "unconnected-(VGA-OPLO-Pad12)") (class "Default")
      (node (ref "VGA") (pin "12") (pinfunction "OPLO_12") (pintype "output"))
    )
    (net (code "84") (name "unconnected-(VGA-VMAG-Pad10)") (class "Default")
      (node (ref "VGA") (pin "10") (pinfunction "VMAG_10") (pintype "input"))
    )
  )
)
